# P07_DDR3_Memory.net
KiCad netlist of a schematic drawn in Altium Designer
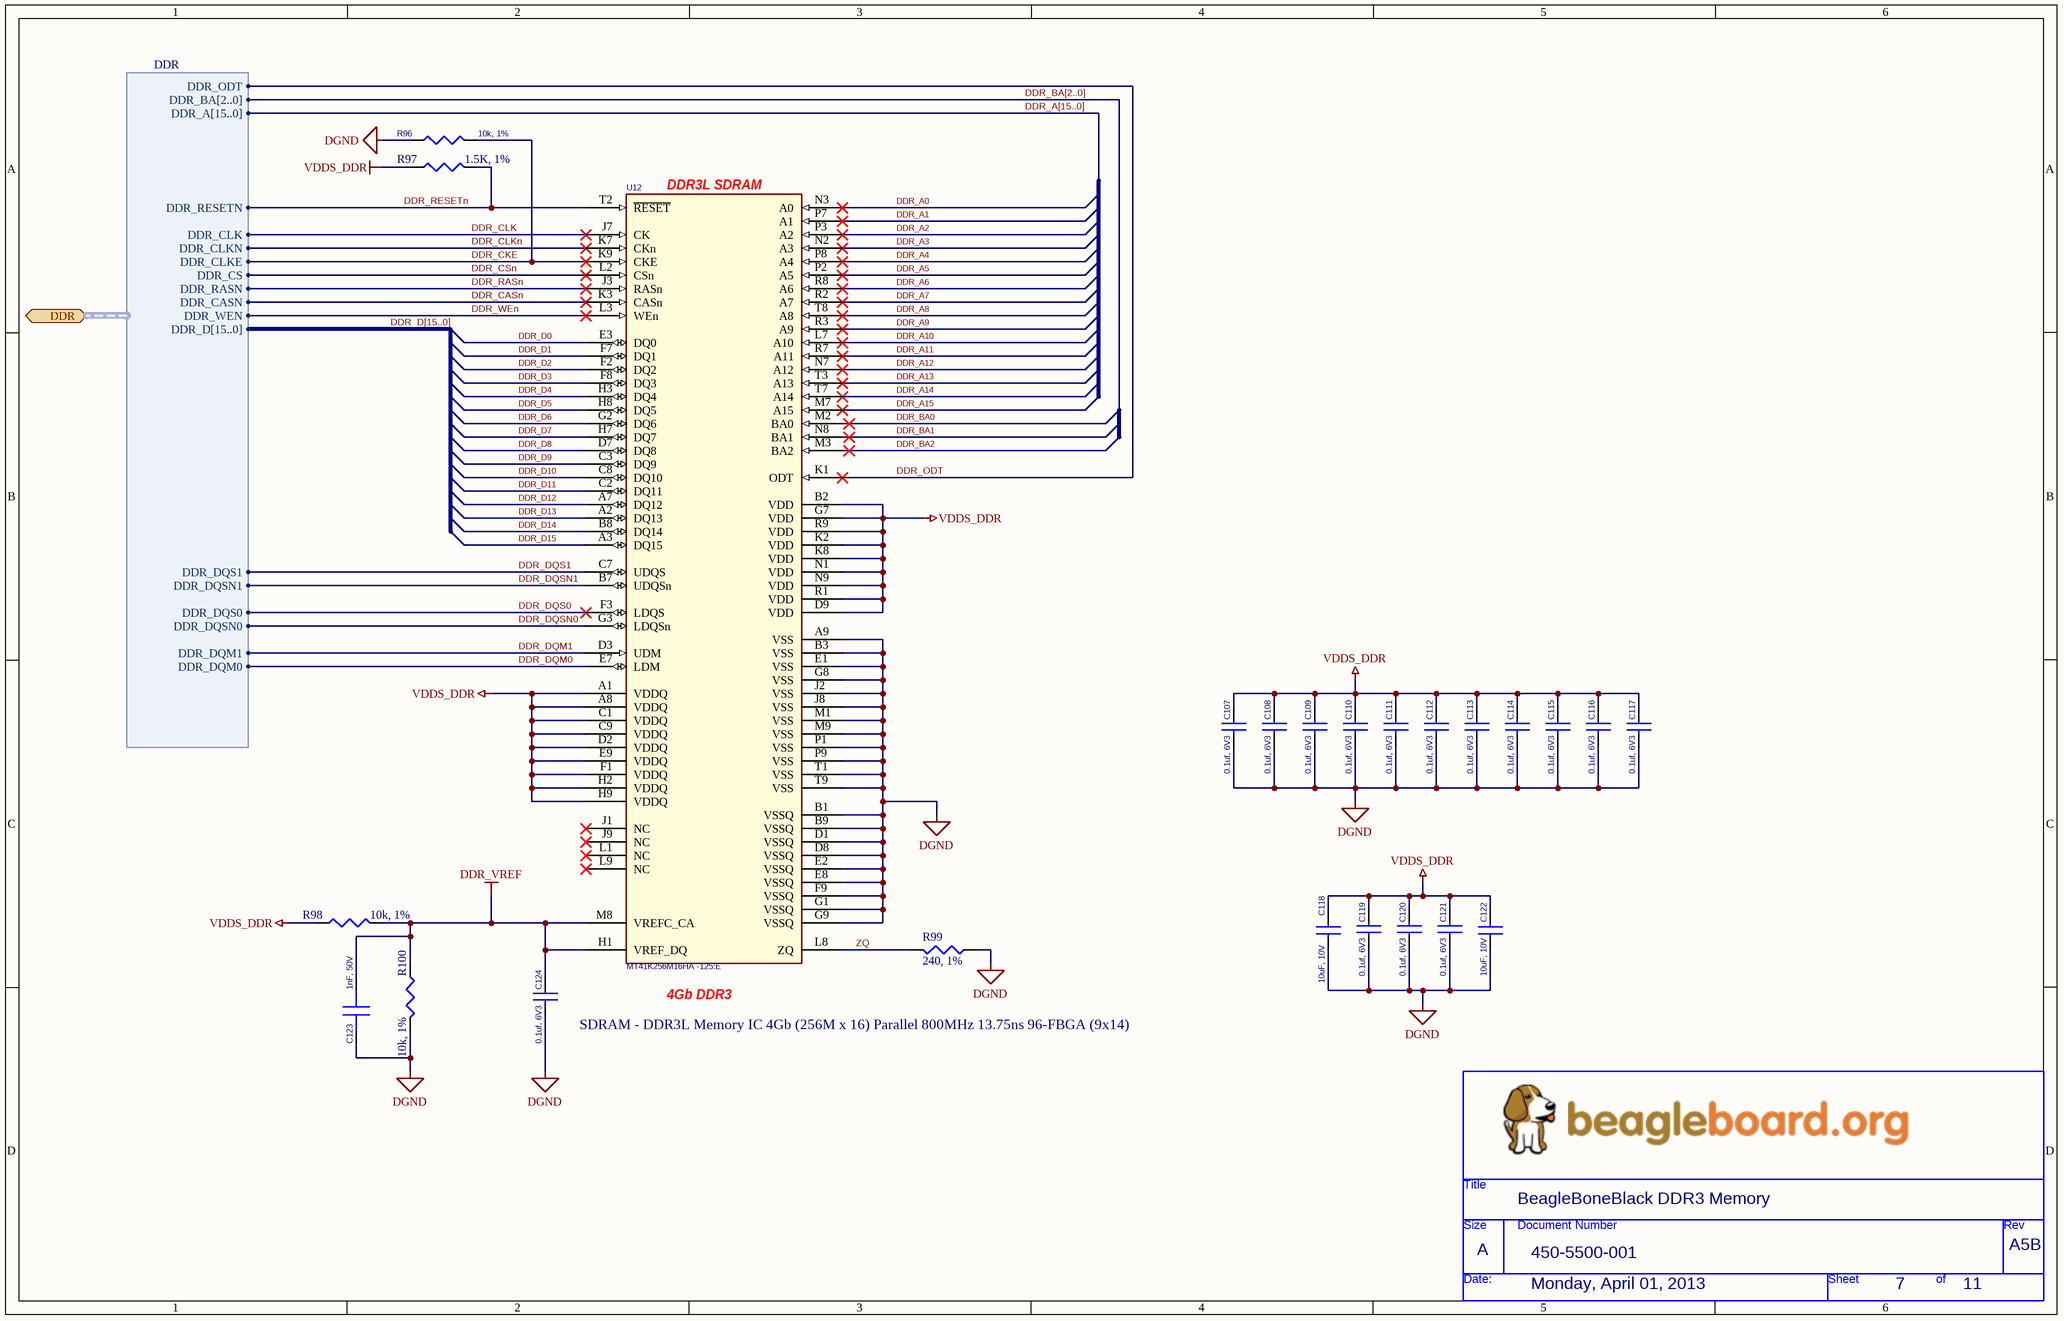
[diagram p0: P07_DDR3 Memory.SchDoc]

(export (version "E")
  (design (tool "Eeschema 10.0.6"))
  (components
    (comp (ref "C107")
      (value "0.1uf, 6V3")
      (footprint "402")
      (description "CAP CER 0.1UF 6.3V 10% X5R 0402")
      (fields
        (field (name "MANUFACTURER") "TDK Corporation")
        (field (name "MANUFACTURER PART NUMBER") "C1005X5R0J104K050BA")
      )
      (libsource (lib "BEAGLEBONEBLACK_REV A5B") (part "CAP_0.01uf_X7R_16V_10%_0402"))
    )
    (comp (ref "C108")
      (value "0.1uf, 6V3")
      (footprint "402")
      (description "CAP CER 0.1UF 6.3V 10% X5R 0402")
      (fields
        (field (name "MANUFACTURER") "TDK Corporation")
        (field (name "MANUFACTURER PART NUMBER") "C1005X5R0J104K050BA")
      )
      (libsource (lib "BEAGLEBONEBLACK_REV A5B") (part "CAP_0.01uf_X7R_16V_10%_0402"))
    )
    (comp (ref "C109")
      (value "0.1uf, 6V3")
      (footprint "402")
      (description "CAP CER 0.1UF 6.3V 10% X5R 0402")
      (fields
        (field (name "MANUFACTURER") "TDK Corporation")
        (field (name "MANUFACTURER PART NUMBER") "C1005X5R0J104K050BA")
      )
      (libsource (lib "BEAGLEBONEBLACK_REV A5B") (part "CAP_0.01uf_X7R_16V_10%_0402"))
    )
    (comp (ref "C110")
      (value "0.1uf, 6V3")
      (footprint "402")
      (description "CAP CER 0.1UF 6.3V 10% X5R 0402")
      (fields
        (field (name "MANUFACTURER") "TDK Corporation")
        (field (name "MANUFACTURER PART NUMBER") "C1005X5R0J104K050BA")
      )
      (libsource (lib "BEAGLEBONEBLACK_REV A5B") (part "CAP_0.01uf_X7R_16V_10%_0402"))
    )
    (comp (ref "C111")
      (value "0.1uf, 6V3")
      (footprint "402")
      (description "CAP CER 0.1UF 6.3V 10% X5R 0402")
      (fields
        (field (name "MANUFACTURER") "TDK Corporation")
        (field (name "MANUFACTURER PART NUMBER") "C1005X5R0J104K050BA")
      )
      (libsource (lib "BEAGLEBONEBLACK_REV A5B") (part "CAP_0.01uf_X7R_16V_10%_0402"))
    )
    (comp (ref "C112")
      (value "0.1uf, 6V3")
      (footprint "402")
      (description "CAP CER 0.1UF 6.3V 10% X5R 0402")
      (fields
        (field (name "MANUFACTURER") "TDK Corporation")
        (field (name "MANUFACTURER PART NUMBER") "C1005X5R0J104K050BA")
      )
      (libsource (lib "BEAGLEBONEBLACK_REV A5B") (part "CAP_0.01uf_X7R_16V_10%_0402"))
    )
    (comp (ref "C113")
      (value "0.1uf, 6V3")
      (footprint "402")
      (description "CAP CER 0.1UF 6.3V 10% X5R 0402")
      (fields
        (field (name "MANUFACTURER") "TDK Corporation")
        (field (name "MANUFACTURER PART NUMBER") "C1005X5R0J104K050BA")
      )
      (libsource (lib "BEAGLEBONEBLACK_REV A5B") (part "CAP_0.01uf_X7R_16V_10%_0402"))
    )
    (comp (ref "C114")
      (value "0.1uf, 6V3")
      (footprint "402")
      (description "CAP CER 0.1UF 6.3V 10% X5R 0402")
      (fields
        (field (name "MANUFACTURER") "TDK Corporation")
        (field (name "MANUFACTURER PART NUMBER") "C1005X5R0J104K050BA")
      )
      (libsource (lib "BEAGLEBONEBLACK_REV A5B") (part "CAP_0.01uf_X7R_16V_10%_0402"))
    )
    (comp (ref "C115")
      (value "0.1uf, 6V3")
      (footprint "402")
      (description "CAP CER 0.1UF 6.3V 10% X5R 0402")
      (fields
        (field (name "MANUFACTURER") "TDK Corporation")
        (field (name "MANUFACTURER PART NUMBER") "C1005X5R0J104K050BA")
      )
      (libsource (lib "BEAGLEBONEBLACK_REV A5B") (part "CAP_0.01uf_X7R_16V_10%_0402"))
    )
    (comp (ref "C116")
      (value "0.1uf, 6V3")
      (footprint "402")
      (description "CAP CER 0.1UF 6.3V 10% X5R 0402")
      (fields
        (field (name "MANUFACTURER") "TDK Corporation")
        (field (name "MANUFACTURER PART NUMBER") "C1005X5R0J104K050BA")
      )
      (libsource (lib "BEAGLEBONEBLACK_REV A5B") (part "CAP_0.01uf_X7R_16V_10%_0402"))
    )
    (comp (ref "C117")
      (value "0.1uf, 6V3")
      (footprint "402")
      (description "CAP CER 0.1UF 6.3V 10% X5R 0402")
      (fields
        (field (name "MANUFACTURER") "TDK Corporation")
        (field (name "MANUFACTURER PART NUMBER") "C1005X5R0J104K050BA")
      )
      (libsource (lib "BEAGLEBONEBLACK_REV A5B") (part "CAP_0.01uf_X7R_16V_10%_0402"))
    )
    (comp (ref "C118")
      (value "10uF, 10V")
      (footprint "805")
      (description "CAP CER 10UF 10V Y5V 0805")
      (fields
        (field (name "MANUFACTURER") "TDK Corporation")
        (field (name "MANUFACTURER PART NUMBER") "C2012Y5V1A106Z")
      )
      (libsource (lib "BEAGLEBONEBLACK_REV A5B") (part "CAP_4.7uF_X5R_6.3V_10%_0603"))
    )
    (comp (ref "C119")
      (value "0.1uf, 6V3")
      (footprint "402")
      (description "CAP CER 0.1UF 6.3V 10% X5R 0402")
      (fields
        (field (name "MANUFACTURER") "TDK Corporation")
        (field (name "MANUFACTURER PART NUMBER") "C1005X5R0J104K050BA")
      )
      (libsource (lib "BEAGLEBONEBLACK_REV A5B") (part "CAP_0.01uf_X7R_16V_10%_0402"))
    )
    (comp (ref "C120")
      (value "0.1uf, 6V3")
      (footprint "402")
      (description "CAP CER 0.1UF 6.3V 10% X5R 0402")
      (fields
        (field (name "MANUFACTURER") "TDK Corporation")
        (field (name "MANUFACTURER PART NUMBER") "C1005X5R0J104K050BA")
      )
      (libsource (lib "BEAGLEBONEBLACK_REV A5B") (part "CAP_0.01uf_X7R_16V_10%_0402"))
    )
    (comp (ref "C121")
      (value "0.1uf, 6V3")
      (footprint "402")
      (description "CAP CER 0.1UF 6.3V 10% X5R 0402")
      (fields
        (field (name "MANUFACTURER") "TDK Corporation")
        (field (name "MANUFACTURER PART NUMBER") "C1005X5R0J104K050BA")
      )
      (libsource (lib "BEAGLEBONEBLACK_REV A5B") (part "CAP_0.01uf_X7R_16V_10%_0402"))
    )
    (comp (ref "C122")
      (value "10uF, 10V")
      (footprint "805")
      (description "CAP CER 10UF 10V Y5V 0805")
      (fields
        (field (name "MANUFACTURER") "TDK Corporation")
        (field (name "MANUFACTURER PART NUMBER") "C2012Y5V1A106Z")
      )
      (libsource (lib "BEAGLEBONEBLACK_REV A5B") (part "CAP_4.7uF_X5R_6.3V_10%_0603"))
    )
    (comp (ref "C123")
      (value "1nF, 50V")
      (footprint "402")
      (description "CAP CER 1000PF 16V 10% X7R 0402")
      (fields
        (field (name "MANUFACTURER") "Yageo")
        (field (name "MANUFACTURER PART NUMBER") "CC0402KRX7R7BB102")
      )
      (libsource (lib "BEAGLEBONEBLACK_REV A5B") (part "CAP SMD"))
    )
    (comp (ref "C124")
      (value "0.1uf, 6V3")
      (footprint "402")
      (description "CAP CER 0.1UF 6.3V 10% X5R 0402")
      (fields
        (field (name "MANUFACTURER") "TDK Corporation")
        (field (name "MANUFACTURER PART NUMBER") "C1005X5R0J104K050BA")
      )
      (libsource (lib "BEAGLEBONEBLACK_REV A5B") (part "CAP_0.01uf_X7R_16V_10%_0402"))
    )
    (comp (ref "R96")
      (value "10k, 1%")
      (footprint "402")
      (description "RES 10K OHM 1/16W 5% 0402 SMD")
      (fields
        (field (name "MANUFACTURER") "Rohm Semiconductor")
        (field (name "MANUFACTURER PART NUMBER") "MCR01MZPJ103")
      )
      (libsource (lib "BEAGLEBONEBLACK_REV A5B") (part "RES_10K_1/16W_1%_0402"))
    )
    (comp (ref "R97")
      (value "1.5K, 1%")
      (footprint "402")
      (description "RES 1.50K OHM 1/16W 1% 0402 SMD")
      (fields
        (field (name "MANUFACTURER") "Yageo")
        (field (name "MANUFACTURER PART NUMBER") "RC0402FR-071K5L")
      )
      (libsource (lib "BEAGLEBONEBLACK_REV A5B") (part "RES_10K_1/16W_1%_0402"))
    )
    (comp (ref "R98")
      (value "10k, 1%")
      (footprint "402")
      (description "RES 10K OHM 1/16W 5% 0402 SMD")
      (fields
        (field (name "MANUFACTURER") "Rohm Semiconductor")
        (field (name "MANUFACTURER PART NUMBER") "MCR01MZPJ103")
      )
      (libsource (lib "BEAGLEBONEBLACK_REV A5B") (part "RES_10K_1/16W_1%_0402"))
    )
    (comp (ref "R99")
      (value "240, 1%")
      (footprint "402")
      (description "RES 240 OHM 1/10W 5% 0402 SMD")
      (fields
        (field (name "MANUFACTURER") "Yageo")
        (field (name "MANUFACTURER PART NUMBER") "RC0402FR-07240RL")
      )
      (libsource (lib "BEAGLEBONEBLACK_REV A5B") (part "RES_10K_1/16W_1%_0402"))
    )
    (comp (ref "R100")
      (value "10k, 1%")
      (footprint "402")
      (description "RES 10K OHM 1/16W 5% 0402 SMD")
      (fields
        (field (name "MANUFACTURER") "Rohm Semiconductor")
        (field (name "MANUFACTURER PART NUMBER") "MCR01MZPJ103")
      )
      (libsource (lib "BEAGLEBONEBLACK_REV A5B") (part "RES_10K_1/16W_1%_0402"))
    )
    (comp (ref "U12")
      (value "MT41K256M16HA -125:E")
      (footprint "BGA96_T9_P8_9X14")
      (description "DDR2 SDRAM 2Gb (256Mx8)")
      (fields
        (field (name "MANUFACTURER") "Micron Technology")
        (field (name "MANUFACTURER PART NUMBER") "MT41K256M16HA-125:E")
      )
      (libsource (lib "BEAGLEBONEBLACK_REV A5B") (part "MT41K256M16HA"))
    )
  )
  (nets
    (net (code "2") (name "/DDR_A0") (class "Default")
      (node (ref "U12") (pin "N3") (pinfunction "A0_N3") (pintype "input+no_connect"))
    )
    (net (code "3") (name "/DDR_A1") (class "Default")
      (node (ref "U12") (pin "P7") (pinfunction "A1_P7") (pintype "input+no_connect"))
    )
    (net (code "4") (name "/DDR_A2") (class "Default")
      (node (ref "U12") (pin "P3") (pinfunction "A2_P3") (pintype "input+no_connect"))
    )
    (net (code "5") (name "/DDR_A3") (class "Default")
      (node (ref "U12") (pin "N2") (pinfunction "A3_N2") (pintype "input+no_connect"))
    )
    (net (code "6") (name "/DDR_A4") (class "Default")
      (node (ref "U12") (pin "P8") (pinfunction "A4_P8") (pintype "input+no_connect"))
    )
    (net (code "7") (name "/DDR_A5") (class "Default")
      (node (ref "U12") (pin "P2") (pinfunction "A5_P2") (pintype "input+no_connect"))
    )
    (net (code "8") (name "/DDR_A6") (class "Default")
      (node (ref "U12") (pin "R8") (pinfunction "A6_R8") (pintype "input+no_connect"))
    )
    (net (code "9") (name "/DDR_A7") (class "Default")
      (node (ref "U12") (pin "R2") (pinfunction "A7_R2") (pintype "input+no_connect"))
    )
    (net (code "10") (name "/DDR_A8") (class "Default")
      (node (ref "U12") (pin "T8") (pinfunction "A8_T8") (pintype "input+no_connect"))
    )
    (net (code "11") (name "/DDR_A9") (class "Default")
      (node (ref "U12") (pin "R3") (pinfunction "A9_R3") (pintype "input+no_connect"))
    )
    (net (code "12") (name "/DDR_A10") (class "Default")
      (node (ref "U12") (pin "L7") (pinfunction "A10_L7") (pintype "input+no_connect"))
    )
    (net (code "13") (name "/DDR_A11") (class "Default")
      (node (ref "U12") (pin "R7") (pinfunction "A11_R7") (pintype "input+no_connect"))
    )
    (net (code "14") (name "/DDR_A12") (class "Default")
      (node (ref "U12") (pin "N7") (pinfunction "A12_N7") (pintype "input+no_connect"))
    )
    (net (code "15") (name "/DDR_A13") (class "Default")
      (node (ref "U12") (pin "T3") (pinfunction "A13_T3") (pintype "input+no_connect"))
    )
    (net (code "16") (name "/DDR_A14") (class "Default")
      (node (ref "U12") (pin "T7") (pinfunction "A14_T7") (pintype "input+no_connect"))
    )
    (net (code "17") (name "/DDR_A15") (class "Default")
      (node (ref "U12") (pin "M7") (pinfunction "A15_M7") (pintype "input+no_connect"))
    )
    (net (code "19") (name "/DDR_BA0") (class "Default")
      (node (ref "U12") (pin "M2") (pinfunction "BA0_M2") (pintype "input"))
    )
    (net (code "20") (name "/DDR_BA1") (class "Default")
      (node (ref "U12") (pin "N8") (pinfunction "BA1_N8") (pintype "input"))
    )
    (net (code "21") (name "/DDR_BA2") (class "Default")
      (node (ref "U12") (pin "M3") (pinfunction "BA2_M3") (pintype "input"))
    )
    (net (code "22") (name "/DDR_CASn") (class "Default")
      (node (ref "U12") (pin "K3") (pinfunction "CASn_K3") (pintype "input+no_connect"))
    )
    (net (code "23") (name "/DDR_CKE") (class "Default")
      (node (ref "R96") (pin "2") (pinfunction "2_2") (pintype "passive"))
      (node (ref "U12") (pin "K9") (pinfunction "CKE_K9") (pintype "input"))
    )
    (net (code "24") (name "/DDR_CLK") (class "Default")
      (node (ref "U12") (pin "J7") (pinfunction "CK_J7") (pintype "input+no_connect"))
    )
    (net (code "25") (name "/DDR_CLKn") (class "Default")
      (node (ref "U12") (pin "K7") (pinfunction "CKn_K7") (pintype "input+no_connect"))
    )
    (net (code "26") (name "/DDR_CSn") (class "Default")
      (node (ref "U12") (pin "L2") (pinfunction "CSn_L2") (pintype "input+no_connect"))
    )
    (net (code "27") (name "/DDR_D0") (class "Default")
      (node (ref "U12") (pin "E3") (pinfunction "DQ0_E3") (pintype "bidirectional"))
    )
    (net (code "28") (name "/DDR_D1") (class "Default")
      (node (ref "U12") (pin "F7") (pinfunction "DQ1_F7") (pintype "bidirectional"))
    )
    (net (code "29") (name "/DDR_D2") (class "Default")
      (node (ref "U12") (pin "F2") (pinfunction "DQ2_F2") (pintype "bidirectional"))
    )
    (net (code "30") (name "/DDR_D3") (class "Default")
      (node (ref "U12") (pin "F8") (pinfunction "DQ3_F8") (pintype "bidirectional"))
    )
    (net (code "31") (name "/DDR_D4") (class "Default")
      (node (ref "U12") (pin "H3") (pinfunction "DQ4_H3") (pintype "bidirectional"))
    )
    (net (code "32") (name "/DDR_D5") (class "Default")
      (node (ref "U12") (pin "H8") (pinfunction "DQ5_H8") (pintype "bidirectional"))
    )
    (net (code "33") (name "/DDR_D6") (class "Default")
      (node (ref "U12") (pin "G2") (pinfunction "DQ6_G2") (pintype "bidirectional"))
    )
    (net (code "34") (name "/DDR_D7") (class "Default")
      (node (ref "U12") (pin "H7") (pinfunction "DQ7_H7") (pintype "bidirectional"))
    )
    (net (code "35") (name "/DDR_D8") (class "Default")
      (node (ref "U12") (pin "D7") (pinfunction "DQ8_D7") (pintype "bidirectional"))
    )
    (net (code "36") (name "/DDR_D9") (class "Default")
      (node (ref "U12") (pin "C3") (pinfunction "DQ9_C3") (pintype "bidirectional"))
    )
    (net (code "37") (name "/DDR_D10") (class "Default")
      (node (ref "U12") (pin "C8") (pinfunction "DQ10_C8") (pintype "bidirectional"))
    )
    (net (code "38") (name "/DDR_D11") (class "Default")
      (node (ref "U12") (pin "C2") (pinfunction "DQ11_C2") (pintype "bidirectional"))
    )
    (net (code "39") (name "/DDR_D12") (class "Default")
      (node (ref "U12") (pin "A7") (pinfunction "DQ12_A7") (pintype "bidirectional"))
    )
    (net (code "40") (name "/DDR_D13") (class "Default")
      (node (ref "U12") (pin "A2") (pinfunction "DQ13_A2") (pintype "bidirectional"))
    )
    (net (code "41") (name "/DDR_D14") (class "Default")
      (node (ref "U12") (pin "B8") (pinfunction "DQ14_B8") (pintype "bidirectional"))
    )
    (net (code "42") (name "/DDR_D15") (class "Default")
      (node (ref "U12") (pin "A3") (pinfunction "DQ15_A3") (pintype "bidirectional"))
    )
    (net (code "43") (name "/DDR_DQM0") (class "Default")
      (node (ref "U12") (pin "E7") (pinfunction "LDM_E7") (pintype "bidirectional"))
    )
    (net (code "44") (name "/DDR_DQM1") (class "Default")
      (node (ref "U12") (pin "D3") (pinfunction "UDM_D3") (pintype "input"))
    )
    (net (code "45") (name "/DDR_DQS0") (class "Default")
      (node (ref "U12") (pin "F3") (pinfunction "LDQS_F3") (pintype "bidirectional+no_connect"))
    )
    (net (code "46") (name "/DDR_DQS1") (class "Default")
      (node (ref "U12") (pin "C7") (pinfunction "UDQS_C7") (pintype "bidirectional"))
    )
    (net (code "47") (name "/DDR_DQSN0") (class "Default")
      (node (ref "U12") (pin "G3") (pinfunction "LDQSn_G3") (pintype "bidirectional"))
    )
    (net (code "48") (name "/DDR_DQSN1") (class "Default")
      (node (ref "U12") (pin "B7") (pinfunction "UDQSn_B7") (pintype "bidirectional"))
    )
    (net (code "50") (name "/DDR_ODT") (class "Default")
      (node (ref "U12") (pin "K1") (pinfunction "ODT_K1") (pintype "input+no_connect"))
    )
    (net (code "51") (name "/DDR_RASn") (class "Default")
      (node (ref "U12") (pin "J3") (pinfunction "RASn_J3") (pintype "input+no_connect"))
    )
    (net (code "52") (name "/DDR_RESETn") (class "Default")
      (node (ref "R97") (pin "2") (pinfunction "2_2") (pintype "passive"))
      (node (ref "U12") (pin "T2") (pinfunction "~{RESET}_T2") (pintype "input"))
    )
    (net (code "53") (name "/DDR_WEn") (class "Default")
      (node (ref "U12") (pin "L3") (pinfunction "WEn_L3") (pintype "input+no_connect"))
    )
    (net (code "55") (name "/ZQ") (class "Default")
      (node (ref "R99") (pin "2") (pinfunction "2_2") (pintype "passive"))
      (node (ref "U12") (pin "L8") (pinfunction "ZQ_L8") (pintype "passive"))
    )
    (net (code "57") (name "DDR_VREF") (class "Default")
      (node (ref "C123") (pin "1") (pinfunction "1_1") (pintype "passive"))
      (node (ref "C124") (pin "1") (pinfunction "1_1") (pintype "passive"))
      (node (ref "R100") (pin "1") (pinfunction "1_1") (pintype "passive"))
      (node (ref "R98") (pin "2") (pinfunction "2_2") (pintype "passive"))
      (node (ref "U12") (pin "H1") (pinfunction "VREF_DQ_H1") (pintype "passive"))
      (node (ref "U12") (pin "M8") (pinfunction "VREFC_CA_M8") (pintype "power_in"))
    )
    (net (code "58") (name "DGND") (class "Default")
      (node (ref "C107") (pin "2") (pinfunction "2_2") (pintype "passive"))
      (node (ref "C108") (pin "2") (pinfunction "2_2") (pintype "passive"))
      (node (ref "C109") (pin "2") (pinfunction "2_2") (pintype "passive"))
      (node (ref "C110") (pin "2") (pinfunction "2_2") (pintype "passive"))
      (node (ref "C111") (pin "2") (pinfunction "2_2") (pintype "passive"))
      (node (ref "C112") (pin "2") (pinfunction "2_2") (pintype "passive"))
      (node (ref "C113") (pin "2") (pinfunction "2_2") (pintype "passive"))
      (node (ref "C114") (pin "2") (pinfunction "2_2") (pintype "passive"))
      (node (ref "C115") (pin "2") (pinfunction "2_2") (pintype "passive"))
      (node (ref "C116") (pin "2") (pinfunction "2_2") (pintype "passive"))
      (node (ref "C117") (pin "2") (pinfunction "2_2") (pintype "passive"))
      (node (ref "C118") (pin "1") (pinfunction "1_1") (pintype "passive"))
      (node (ref "C119") (pin "2") (pinfunction "2_2") (pintype "passive"))
      (node (ref "C120") (pin "2") (pinfunction "2_2") (pintype "passive"))
      (node (ref "C121") (pin "2") (pinfunction "2_2") (pintype "passive"))
      (node (ref "C122") (pin "1") (pinfunction "1_1") (pintype "passive"))
      (node (ref "C123") (pin "2") (pinfunction "2_2") (pintype "passive"))
      (node (ref "C124") (pin "2") (pinfunction "2_2") (pintype "passive"))
      (node (ref "R100") (pin "2") (pinfunction "2_2") (pintype "passive"))
      (node (ref "R96") (pin "1") (pinfunction "1_1") (pintype "passive"))
      (node (ref "R99") (pin "1") (pinfunction "1_1") (pintype "passive"))
      (node (ref "U12") (pin "A9") (pinfunction "VSS_A9") (pintype "power_in"))
      (node (ref "U12") (pin "B1") (pinfunction "VSSQ_B1") (pintype "power_in"))
      (node (ref "U12") (pin "B3") (pinfunction "VSS_B3") (pintype "power_in"))
      (node (ref "U12") (pin "B9") (pinfunction "VSSQ_B9") (pintype "power_in"))
      (node (ref "U12") (pin "D1") (pinfunction "VSSQ_D1") (pintype "power_in"))
      (node (ref "U12") (pin "D8") (pinfunction "VSSQ_D8") (pintype "power_in"))
      (node (ref "U12") (pin "E1") (pinfunction "VSS_E1") (pintype "power_in"))
      (node (ref "U12") (pin "E2") (pinfunction "VSSQ_E2") (pintype "power_in"))
      (node (ref "U12") (pin "E8") (pinfunction "VSSQ_E8") (pintype "power_in"))
      (node (ref "U12") (pin "F9") (pinfunction "VSSQ_F9") (pintype "power_in"))
      (node (ref "U12") (pin "G1") (pinfunction "VSSQ_G1") (pintype "power_in"))
      (node (ref "U12") (pin "G8") (pinfunction "VSS_G8") (pintype "power_in"))
      (node (ref "U12") (pin "G9") (pinfunction "VSSQ_G9") (pintype "power_in"))
      (node (ref "U12") (pin "J2") (pinfunction "VSS_J2") (pintype "power_in"))
      (node (ref "U12") (pin "J8") (pinfunction "VSS_J8") (pintype "power_in"))
      (node (ref "U12") (pin "M1") (pinfunction "VSS_M1") (pintype "power_in"))
      (node (ref "U12") (pin "M9") (pinfunction "VSS_M9") (pintype "power_in"))
      (node (ref "U12") (pin "P1") (pinfunction "VSS_P1") (pintype "power_in"))
      (node (ref "U12") (pin "P9") (pinfunction "VSS_P9") (pintype "power_in"))
      (node (ref "U12") (pin "T1") (pinfunction "VSS_T1") (pintype "power_in"))
      (node (ref "U12") (pin "T9") (pinfunction "VSS_T9") (pintype "power_in"))
    )
    (net (code "59") (name "VDDS_DDR") (class "Default")
      (node (ref "C107") (pin "1") (pinfunction "1_1") (pintype "passive"))
      (node (ref "C108") (pin "1") (pinfunction "1_1") (pintype "passive"))
      (node (ref "C109") (pin "1") (pinfunction "1_1") (pintype "passive"))
      (node (ref "C110") (pin "1") (pinfunction "1_1") (pintype "passive"))
      (node (ref "C111") (pin "1") (pinfunction "1_1") (pintype "passive"))
      (node (ref "C112") (pin "1") (pinfunction "1_1") (pintype "passive"))
      (node (ref "C113") (pin "1") (pinfunction "1_1") (pintype "passive"))
      (node (ref "C114") (pin "1") (pinfunction "1_1") (pintype "passive"))
      (node (ref "C115") (pin "1") (pinfunction "1_1") (pintype "passive"))
      (node (ref "C116") (pin "1") (pinfunction "1_1") (pintype "passive"))
      (node (ref "C117") (pin "1") (pinfunction "1_1") (pintype "passive"))
      (node (ref "C118") (pin "2") (pinfunction "2_2") (pintype "passive"))
      (node (ref "C119") (pin "1") (pinfunction "1_1") (pintype "passive"))
      (node (ref "C120") (pin "1") (pinfunction "1_1") (pintype "passive"))
      (node (ref "C121") (pin "1") (pinfunction "1_1") (pintype "passive"))
      (node (ref "C122") (pin "2") (pinfunction "2_2") (pintype "passive"))
      (node (ref "R97") (pin "1") (pinfunction "1_1") (pintype "passive"))
      (node (ref "R98") (pin "1") (pinfunction "1_1") (pintype "passive"))
      (node (ref "U12") (pin "A1") (pinfunction "VDDQ_A1") (pintype "power_in"))
      (node (ref "U12") (pin "A8") (pinfunction "VDDQ_A8") (pintype "power_in"))
      (node (ref "U12") (pin "B2") (pinfunction "VDD_B2") (pintype "power_in"))
      (node (ref "U12") (pin "C1") (pinfunction "VDDQ_C1") (pintype "power_in"))
      (node (ref "U12") (pin "C9") (pinfunction "VDDQ_C9") (pintype "power_in"))
      (node (ref "U12") (pin "D2") (pinfunction "VDDQ_D2") (pintype "power_in"))
      (node (ref "U12") (pin "D9") (pinfunction "VDD_D9") (pintype "power_in"))
      (node (ref "U12") (pin "E9") (pinfunction "VDDQ_E9") (pintype "power_in"))
      (node (ref "U12") (pin "F1") (pinfunction "VDDQ_F1") (pintype "power_in"))
      (node (ref "U12") (pin "G7") (pinfunction "VDD_G7") (pintype "power_in"))
      (node (ref "U12") (pin "H2") (pinfunction "VDDQ_H2") (pintype "power_in"))
      (node (ref "U12") (pin "H9") (pinfunction "VDDQ_H9") (pintype "power_in"))
      (node (ref "U12") (pin "K2") (pinfunction "VDD_K2") (pintype "power_in"))
      (node (ref "U12") (pin "K8") (pinfunction "VDD_K8") (pintype "power_in"))
      (node (ref "U12") (pin "N1") (pinfunction "VDD_N1") (pintype "power_in"))
      (node (ref "U12") (pin "N9") (pinfunction "VDD_N9") (pintype "power_in"))
      (node (ref "U12") (pin "R1") (pinfunction "VDD_R1") (pintype "power_in"))
      (node (ref "U12") (pin "R9") (pinfunction "VDD_R9") (pintype "power_in"))
    )
    (net (code "60") (name "unconnected-(U12-NC-PadJ1)") (class "Default")
      (node (ref "U12") (pin "J1") (pinfunction "NC_J1") (pintype "passive+no_connect"))
    )
    (net (code "61") (name "unconnected-(U12-NC-PadJ9)") (class "Default")
      (node (ref "U12") (pin "J9") (pinfunction "NC_J9") (pintype "passive+no_connect"))
    )
    (net (code "62") (name "unconnected-(U12-NC-PadL1)") (class "Default")
      (node (ref "U12") (pin "L1") (pinfunction "NC_L1") (pintype "power_in+no_connect"))
    )
    (net (code "63") (name "unconnected-(U12-NC-PadL9)") (class "Default")
      (node (ref "U12") (pin "L9") (pinfunction "NC_L9") (pintype "power_in+no_connect"))
    )
  )
)
